# QCLogic_Rev_A_Sht6_Connector.net
KiCad netlist of a schematic drawn in Altium Designer
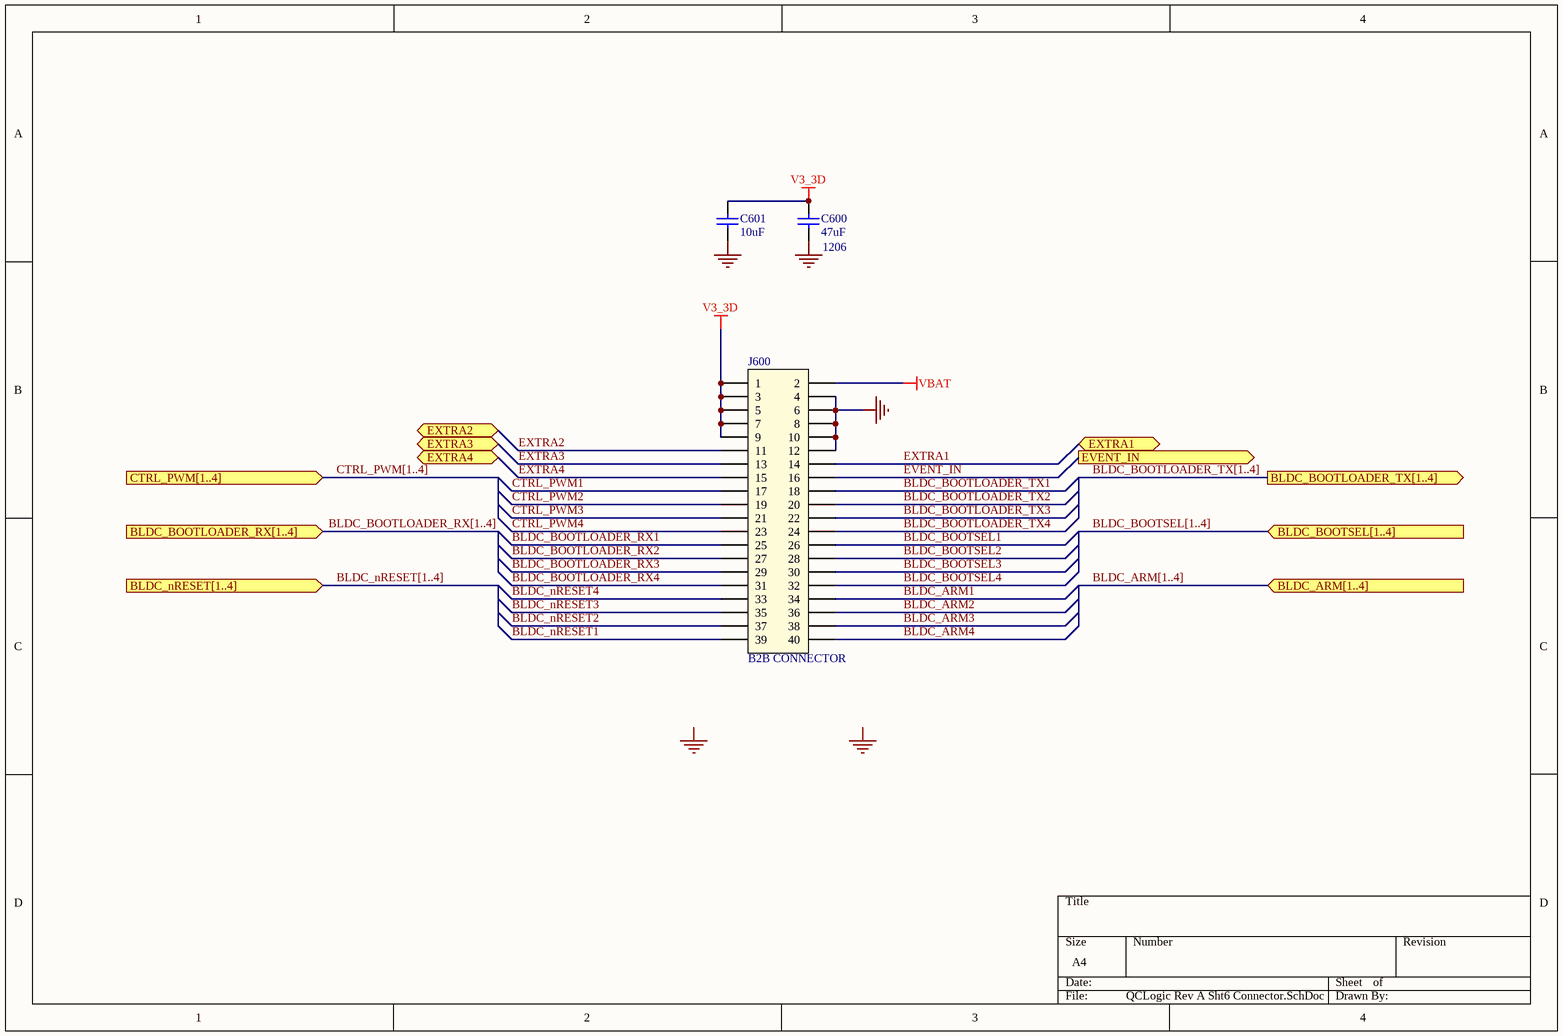
[diagram p0: QCLogic Rev A Sht6 Connector.SchDoc]

(export (version "E")
  (design (tool "Eeschema 10.0.6"))
  (components
    (comp (ref "C600")
      (value "47uF")
      (footprint "SMD CAP 1206")
      (description "CAP CER 47UF 10V X5R 1206")
      (fields
        (field (name "2. MANUFACTURER PART NUMBER") "CL31A476MPHNNNE")
        (field (name "4. PACKAGE") "1206")
      )
      (libsource (lib "SBCLib") (part "CAP MLCC SMD"))
    )
    (comp (ref "C601")
      (value "10uF")
      (footprint "SMD CAP 0805")
      (description "CAP CER 10UF 25V X5R 0805")
      (fields (field (name "2. MANUFACTURER PART NUMBER") "TMK212BBJ106KG-T"))
      (libsource (lib "SBCLib") (part "CAP MLCC SMD"))
    )
    (comp (ref "J600")
      (value "B2B CONNECTOR")
      (footprint "CONN B2B RECPT 40POS SMD GOLD")
      (description "40 Position Connector Receptacle, Outer Shroud Contacts Surface Mount Gold")
      (fields (field (name "2. MANUFACTURER PART NUMBER") "10144517-041802LF"))
      (libsource (lib "SBCLib") (part "CONN B2B RCPT 40POS SMD GOLD"))
    )
  )
  (nets
    (net (code "1") (name "/BLDC_ARM1") (class "Default")
      (node (ref "J600") (pin "34") (pinfunction "34_34") (pintype "passive"))
    )
    (net (code "2") (name "/BLDC_ARM2") (class "Default")
      (node (ref "J600") (pin "36") (pinfunction "36_36") (pintype "passive"))
    )
    (net (code "3") (name "/BLDC_ARM3") (class "Default")
      (node (ref "J600") (pin "38") (pinfunction "38_38") (pintype "passive"))
    )
    (net (code "4") (name "/BLDC_ARM4") (class "Default")
      (node (ref "J600") (pin "40") (pinfunction "40_40") (pintype "passive"))
    )
    (net (code "6") (name "/BLDC_BOOTLOADER_RX1") (class "Default")
      (node (ref "J600") (pin "25") (pinfunction "25_25") (pintype "passive"))
    )
    (net (code "7") (name "/BLDC_BOOTLOADER_RX2") (class "Default")
      (node (ref "J600") (pin "27") (pinfunction "27_27") (pintype "passive"))
    )
    (net (code "8") (name "/BLDC_BOOTLOADER_RX3") (class "Default")
      (node (ref "J600") (pin "29") (pinfunction "29_29") (pintype "passive"))
    )
    (net (code "9") (name "/BLDC_BOOTLOADER_RX4") (class "Default")
      (node (ref "J600") (pin "31") (pinfunction "31_31") (pintype "passive"))
    )
    (net (code "11") (name "/BLDC_BOOTLOADER_TX1") (class "Default")
      (node (ref "J600") (pin "18") (pinfunction "18_18") (pintype "passive"))
    )
    (net (code "12") (name "/BLDC_BOOTLOADER_TX2") (class "Default")
      (node (ref "J600") (pin "20") (pinfunction "20_20") (pintype "passive"))
    )
    (net (code "13") (name "/BLDC_BOOTLOADER_TX3") (class "Default")
      (node (ref "J600") (pin "22") (pinfunction "22_22") (pintype "passive"))
    )
    (net (code "14") (name "/BLDC_BOOTLOADER_TX4") (class "Default")
      (node (ref "J600") (pin "24") (pinfunction "24_24") (pintype "passive"))
    )
    (net (code "16") (name "/BLDC_BOOTSEL1") (class "Default")
      (node (ref "J600") (pin "26") (pinfunction "26_26") (pintype "passive"))
    )
    (net (code "17") (name "/BLDC_BOOTSEL2") (class "Default")
      (node (ref "J600") (pin "28") (pinfunction "28_28") (pintype "passive"))
    )
    (net (code "18") (name "/BLDC_BOOTSEL3") (class "Default")
      (node (ref "J600") (pin "30") (pinfunction "30_30") (pintype "passive"))
    )
    (net (code "19") (name "/BLDC_BOOTSEL4") (class "Default")
      (node (ref "J600") (pin "32") (pinfunction "32_32") (pintype "passive"))
    )
    (net (code "21") (name "/BLDC_nRESET1") (class "Default")
      (node (ref "J600") (pin "39") (pinfunction "39_39") (pintype "passive"))
    )
    (net (code "22") (name "/BLDC_nRESET2") (class "Default")
      (node (ref "J600") (pin "37") (pinfunction "37_37") (pintype "passive"))
    )
    (net (code "23") (name "/BLDC_nRESET3") (class "Default")
      (node (ref "J600") (pin "35") (pinfunction "35_35") (pintype "passive"))
    )
    (net (code "24") (name "/BLDC_nRESET4") (class "Default")
      (node (ref "J600") (pin "33") (pinfunction "33_33") (pintype "passive"))
    )
    (net (code "26") (name "/CTRL_PWM1") (class "Default")
      (node (ref "J600") (pin "17") (pinfunction "17_17") (pintype "passive"))
    )
    (net (code "27") (name "/CTRL_PWM2") (class "Default")
      (node (ref "J600") (pin "19") (pinfunction "19_19") (pintype "passive"))
    )
    (net (code "28") (name "/CTRL_PWM3") (class "Default")
      (node (ref "J600") (pin "21") (pinfunction "21_21") (pintype "passive"))
    )
    (net (code "29") (name "/CTRL_PWM4") (class "Default")
      (node (ref "J600") (pin "23") (pinfunction "23_23") (pintype "passive"))
    )
    (net (code "31") (name "/EVENT_IN") (class "Default")
      (node (ref "J600") (pin "16") (pinfunction "16_16") (pintype "passive"))
    )
    (net (code "32") (name "/EXTRA1") (class "Default")
      (node (ref "J600") (pin "14") (pinfunction "14_14") (pintype "passive"))
    )
    (net (code "33") (name "/EXTRA2") (class "Default")
      (node (ref "J600") (pin "11") (pinfunction "11_11") (pintype "passive"))
    )
    (net (code "34") (name "/EXTRA3") (class "Default")
      (node (ref "J600") (pin "13") (pinfunction "13_13") (pintype "passive"))
    )
    (net (code "35") (name "/EXTRA4") (class "Default")
      (node (ref "J600") (pin "15") (pinfunction "15_15") (pintype "passive"))
    )
    (net (code "36") (name "GND") (class "Default")
      (node (ref "C600") (pin "2") (pinfunction "2_2") (pintype "passive"))
      (node (ref "C601") (pin "2") (pinfunction "2_2") (pintype "passive"))
      (node (ref "J600") (pin "10") (pinfunction "10_10") (pintype "passive"))
      (node (ref "J600") (pin "12") (pinfunction "12_12") (pintype "passive"))
      (node (ref "J600") (pin "4") (pinfunction "4_4") (pintype "passive"))
      (node (ref "J600") (pin "6") (pinfunction "6_6") (pintype "passive"))
      (node (ref "J600") (pin "8") (pinfunction "8_8") (pintype "passive"))
    )
    (net (code "37") (name "V3_3D") (class "Default")
      (node (ref "C600") (pin "1") (pinfunction "1_1") (pintype "passive"))
      (node (ref "C601") (pin "1") (pinfunction "1_1") (pintype "passive"))
      (node (ref "J600") (pin "1") (pinfunction "1_1") (pintype "passive"))
      (node (ref "J600") (pin "3") (pinfunction "3_3") (pintype "passive"))
      (node (ref "J600") (pin "5") (pinfunction "5_5") (pintype "passive"))
      (node (ref "J600") (pin "7") (pinfunction "7_7") (pintype "passive"))
      (node (ref "J600") (pin "9") (pinfunction "9_9") (pintype "passive"))
    )
    (net (code "38") (name "VBAT") (class "Default")
      (node (ref "J600") (pin "2") (pinfunction "2_2") (pintype "passive"))
    )
  )
)
